# G474VET6_Penguins_v1_0.net
KiCad netlist of a schematic drawn in EasyEDA Pro
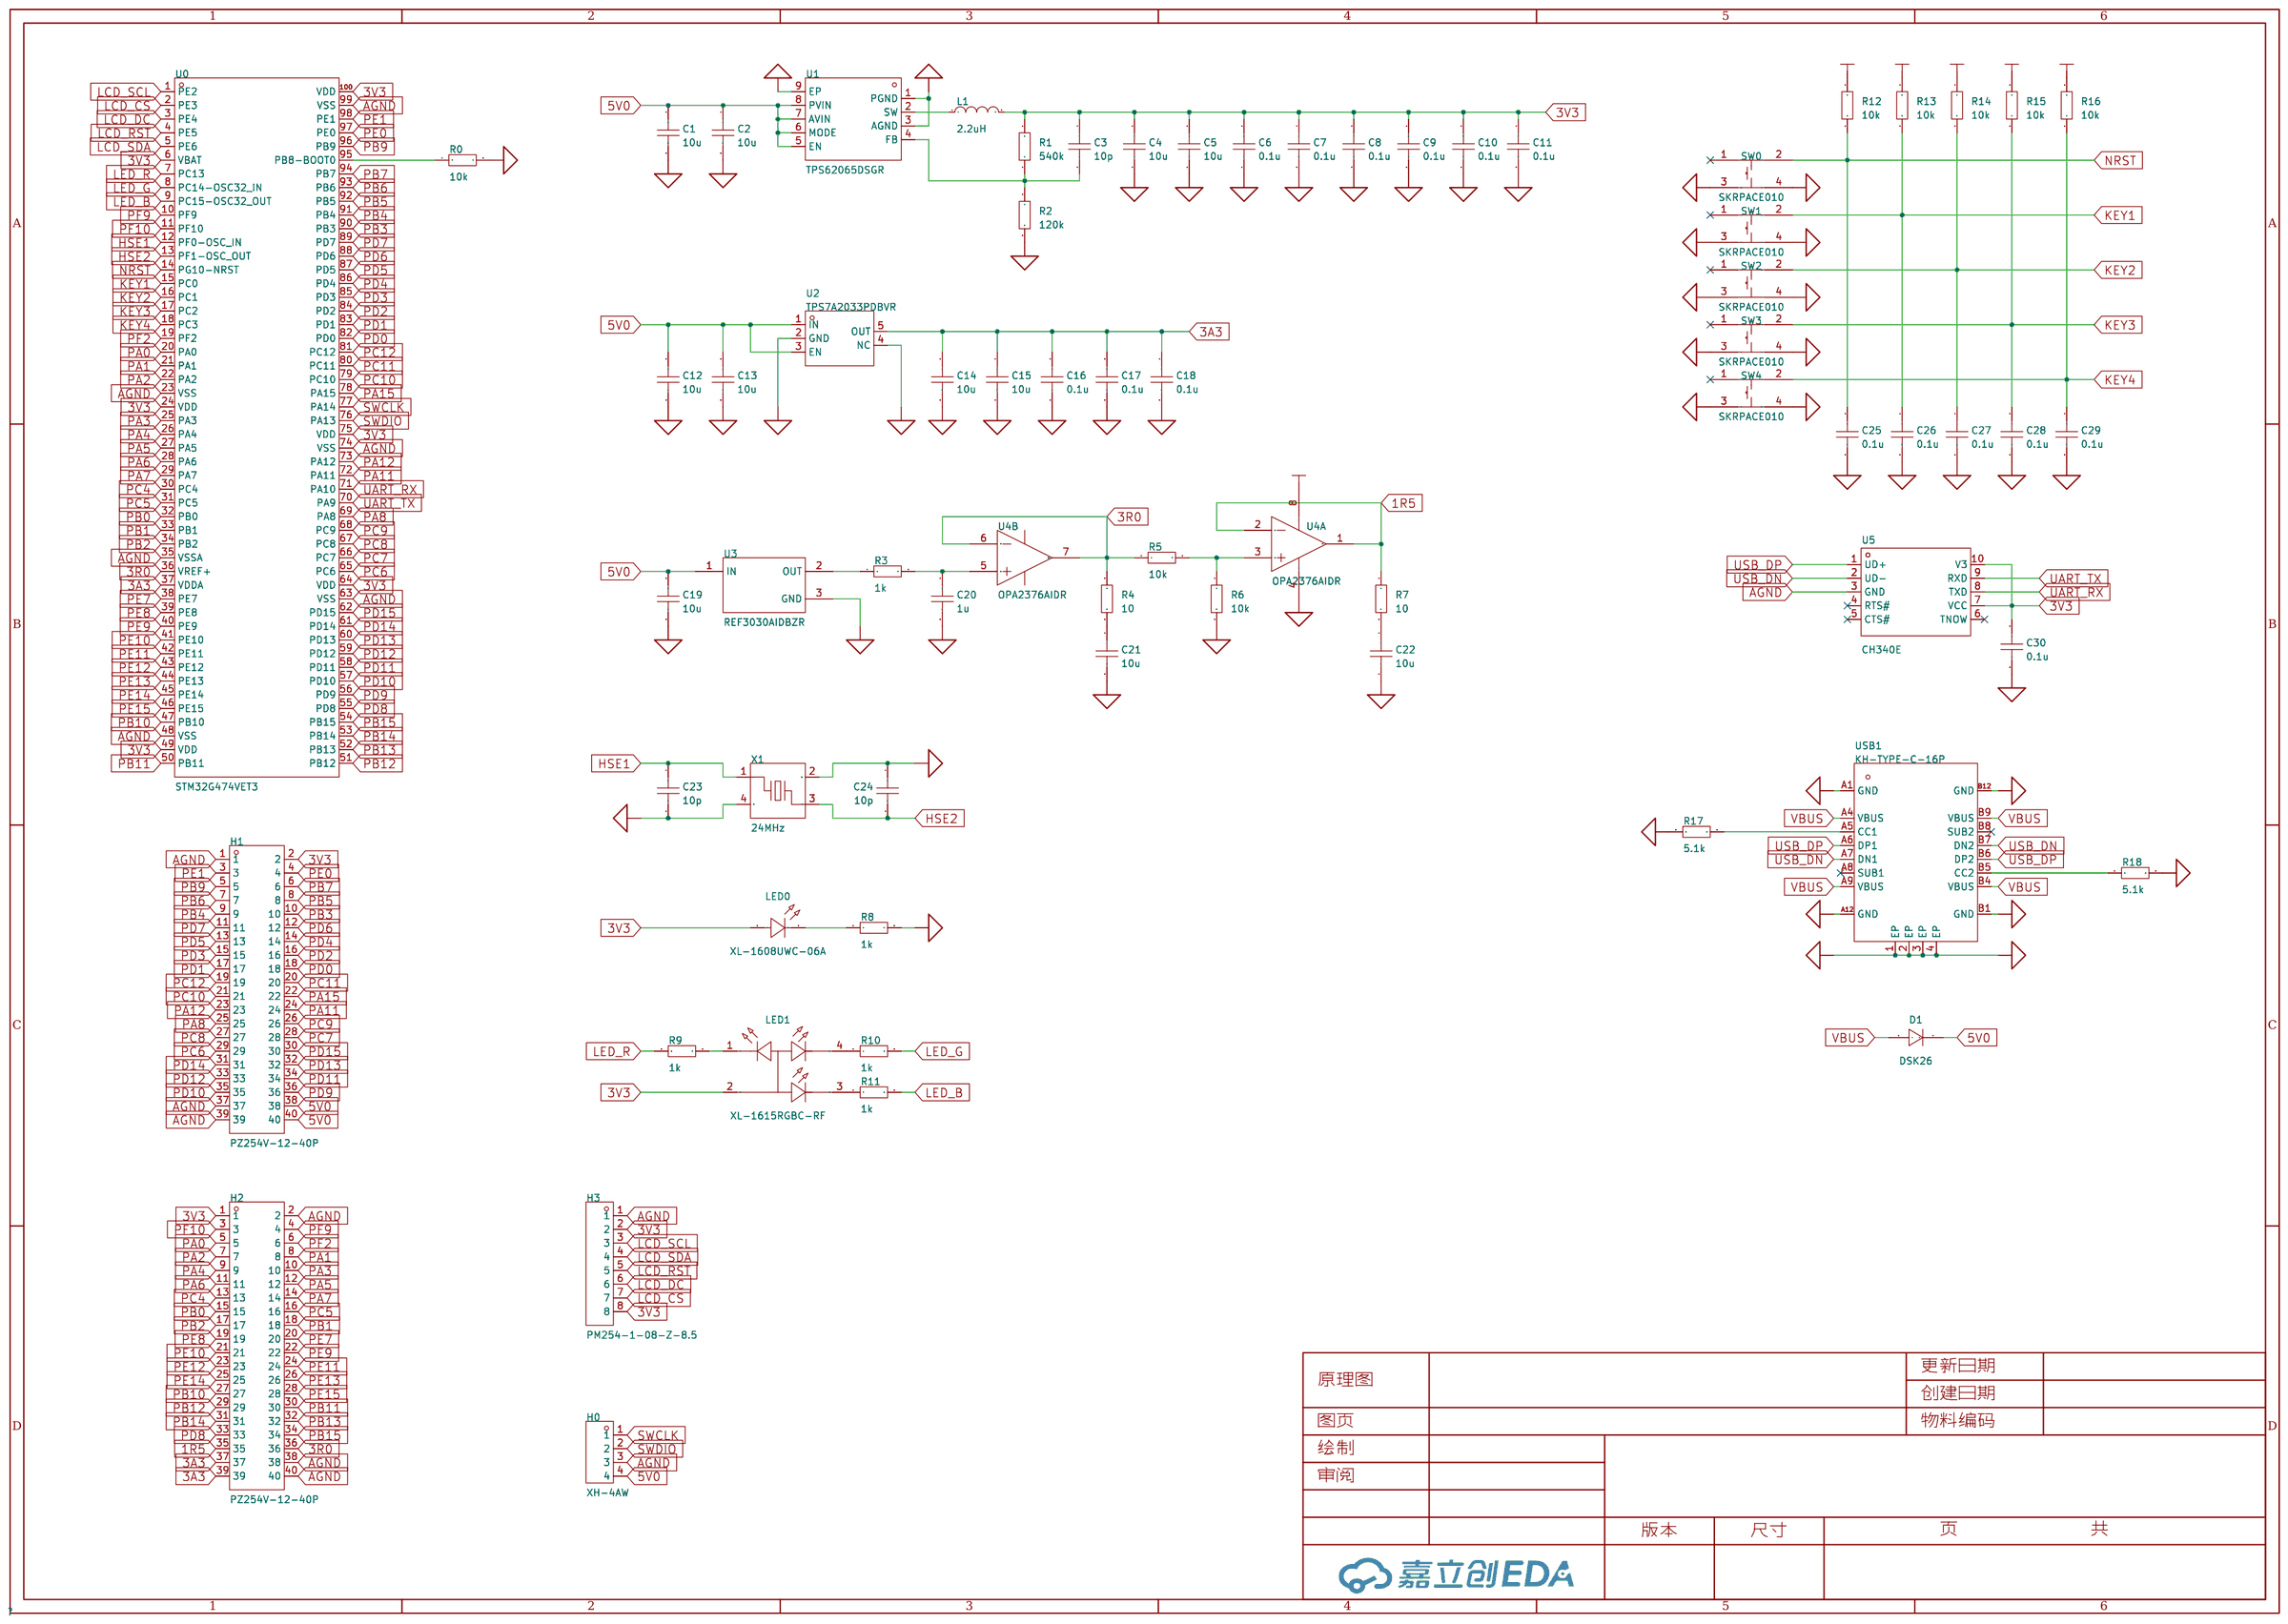
[diagram p0: schematic sheet]

(export (version "E")
  (design (tool "Eeschema 10.0.6"))
  (components
    (comp (ref "C1")
      (value "10u")
      (footprint "easyedapro:C0603")
      (libsource (lib "easyedapro") (part "CapAcitance"))
    )
    (comp (ref "C2")
      (value "10u")
      (footprint "easyedapro:C0603")
      (libsource (lib "easyedapro") (part "CapAcitance"))
    )
    (comp (ref "C3")
      (value "10p")
      (footprint "easyedapro:C0603")
      (libsource (lib "easyedapro") (part "CapAcitance"))
    )
    (comp (ref "C4")
      (value "10u")
      (footprint "easyedapro:C0603")
      (libsource (lib "easyedapro") (part "CapAcitance"))
    )
    (comp (ref "C5")
      (value "10u")
      (footprint "easyedapro:C0603")
      (libsource (lib "easyedapro") (part "CapAcitance"))
    )
    (comp (ref "C6")
      (value "0.1u")
      (footprint "easyedapro:C0603")
      (libsource (lib "easyedapro") (part "CapAcitance"))
    )
    (comp (ref "C7")
      (value "0.1u")
      (footprint "easyedapro:C0603")
      (libsource (lib "easyedapro") (part "CapAcitance"))
    )
    (comp (ref "C8")
      (value "0.1u")
      (footprint "easyedapro:C0603")
      (libsource (lib "easyedapro") (part "CapAcitance"))
    )
    (comp (ref "C9")
      (value "0.1u")
      (footprint "easyedapro:C0603")
      (libsource (lib "easyedapro") (part "CapAcitance"))
    )
    (comp (ref "C10")
      (value "0.1u")
      (footprint "easyedapro:C0603")
      (libsource (lib "easyedapro") (part "CapAcitance"))
    )
    (comp (ref "C11")
      (value "0.1u")
      (footprint "easyedapro:C0603")
      (libsource (lib "easyedapro") (part "CapAcitance"))
    )
    (comp (ref "C12")
      (value "10u")
      (footprint "easyedapro:C0603")
      (libsource (lib "easyedapro") (part "CapAcitance"))
    )
    (comp (ref "C13")
      (value "10u")
      (footprint "easyedapro:C0603")
      (libsource (lib "easyedapro") (part "CapAcitance"))
    )
    (comp (ref "C14")
      (value "10u")
      (footprint "easyedapro:C0603")
      (libsource (lib "easyedapro") (part "CapAcitance"))
    )
    (comp (ref "C15")
      (value "10u")
      (footprint "easyedapro:C0603")
      (libsource (lib "easyedapro") (part "CapAcitance"))
    )
    (comp (ref "C16")
      (value "0.1u")
      (footprint "easyedapro:C0603")
      (libsource (lib "easyedapro") (part "CapAcitance"))
    )
    (comp (ref "C17")
      (value "0.1u")
      (footprint "easyedapro:C0603")
      (libsource (lib "easyedapro") (part "CapAcitance"))
    )
    (comp (ref "C18")
      (value "0.1u")
      (footprint "easyedapro:C0603")
      (libsource (lib "easyedapro") (part "CapAcitance"))
    )
    (comp (ref "C19")
      (value "10u")
      (footprint "easyedapro:C0603")
      (libsource (lib "easyedapro") (part "CapAcitance"))
    )
    (comp (ref "C20")
      (value "1u")
      (footprint "easyedapro:C0603")
      (libsource (lib "easyedapro") (part "CapAcitance"))
    )
    (comp (ref "C21")
      (value "10u")
      (footprint "easyedapro:C0603")
      (libsource (lib "easyedapro") (part "CapAcitance"))
    )
    (comp (ref "C22")
      (value "10u")
      (footprint "easyedapro:C0603")
      (libsource (lib "easyedapro") (part "CapAcitance"))
    )
    (comp (ref "C23")
      (value "10p")
      (footprint "easyedapro:C0603")
      (libsource (lib "easyedapro") (part "CapAcitance"))
    )
    (comp (ref "C24")
      (value "10p")
      (footprint "easyedapro:C0603")
      (libsource (lib "easyedapro") (part "CapAcitance"))
    )
    (comp (ref "C25")
      (value "0.1u")
      (footprint "easyedapro:C0603")
      (libsource (lib "easyedapro") (part "CapAcitance"))
    )
    (comp (ref "C26")
      (value "0.1u")
      (footprint "easyedapro:C0603")
      (libsource (lib "easyedapro") (part "CapAcitance"))
    )
    (comp (ref "C27")
      (value "0.1u")
      (footprint "easyedapro:C0603")
      (libsource (lib "easyedapro") (part "CapAcitance"))
    )
    (comp (ref "C28")
      (value "0.1u")
      (footprint "easyedapro:C0603")
      (libsource (lib "easyedapro") (part "CapAcitance"))
    )
    (comp (ref "C29")
      (value "0.1u")
      (footprint "easyedapro:C0603")
      (libsource (lib "easyedapro") (part "CapAcitance"))
    )
    (comp (ref "C30")
      (value "0.1u")
      (footprint "easyedapro:C0603")
      (libsource (lib "easyedapro") (part "CapAcitance"))
    )
    (comp (ref "D1")
      (value "DSK26")
      (footprint "easyedapro:SOD-123_L2.8-W1.8-LS3.7-RD")
      (description "二极管配置:独立式;正向压降(Vf):700mV@2A;直流反向耐压(Vr):60V;整流电流:2A;")
      (fields (field (name "Manufacturer") "MDD(辰达半导体)"))
      (libsource (lib "easyedapro") (part "DSK26"))
    )
    (comp (ref "H0")
      (value "XH-4AW")
      (footprint "easyedapro:CONN-TH_XH-4AW")
      (fields (field (name "Manufacturer") "HCTL(华灿天禄)"))
      (libsource (lib "easyedapro") (part "XH-4AW_C2908613"))
    )
    (comp (ref "H1")
      (value "PZ254V-12-40P")
      (footprint "easyedapro:HDR-TH_40P-P2.54-V-M-R2-C20-S2.54_2-146257-0")
      (fields (field (name "Manufacturer") "XFCN(兴飞)"))
      (libsource (lib "easyedapro") (part "PZ254V-12-40P"))
    )
    (comp (ref "H2")
      (value "PZ254V-12-40P")
      (footprint "easyedapro:HDR-TH_40P-P2.54-V-M-R2-C20-S2.54_2-146257-0")
      (fields (field (name "Manufacturer") "XFCN(兴飞)"))
      (libsource (lib "easyedapro") (part "PZ254V-12-40P"))
    )
    (comp (ref "H3")
      (value "PM254-1-08-Z-8.5")
      (footprint "easyedapro:HDR-TH_8P-P2.54-V-F")
      (fields (field (name "Manufacturer") "HCTL(华灿天禄)"))
      (libsource (lib "easyedapro") (part "PM254-1-08-Z-8.5"))
    )
    (comp (ref "L1")
      (value "2.2uH")
      (footprint "easyedapro:IND-SMD_L2.5-W2.0")
      (description "电感值:2.2uH;精度:±20%;饱和电流(Isat):3A;类型:-;")
      (fields (field (name "Manufacturer Part") "SMMS252010-2R2M") (field (name "Manufacturer") "SXN(顺翔诺)"))
      (libsource (lib "easyedapro") (part "SMMS252010-2R2M"))
    )
    (comp (ref "LED0")
      (value "XL-1608UWC-06A")
      (footprint "easyedapro:LED0603-RD_1")
      (fields (field (name "Manufacturer") "XINGLIGHT(成兴光)"))
      (libsource (lib "easyedapro") (part "XL-1608UWC-06A"))
    )
    (comp (ref "LED1")
      (value "XL-1615RGBC-RF")
      (footprint "easyedapro:LED-ARRAY-SMD_4P-L1.6-W1.5-BR_XL-1615RGBC-RF")
      (fields (field (name "Manufacturer") "XINGLIGHT(成兴光)"))
      (libsource (lib "easyedapro") (part "XL-1615RGBC-RF"))
    )
    (comp (ref "R0") (value "10k") (footprint "easyedapro:R0603") (libsource (lib "easyedapro") (part "电阻")))
    (comp (ref "R1") (value "540k") (footprint "easyedapro:R0603") (libsource (lib "easyedapro") (part "电阻")))
    (comp (ref "R2") (value "120k") (footprint "easyedapro:R0603") (libsource (lib "easyedapro") (part "电阻")))
    (comp (ref "R3") (value "1k") (footprint "easyedapro:R0603") (libsource (lib "easyedapro") (part "电阻")))
    (comp (ref "R4") (value "10") (footprint "easyedapro:R0603") (libsource (lib "easyedapro") (part "电阻")))
    (comp (ref "R5") (value "10k") (footprint "easyedapro:R0603") (libsource (lib "easyedapro") (part "电阻")))
    (comp (ref "R6") (value "10k") (footprint "easyedapro:R0603") (libsource (lib "easyedapro") (part "电阻")))
    (comp (ref "R7") (value "10") (footprint "easyedapro:R0603") (libsource (lib "easyedapro") (part "电阻")))
    (comp (ref "R8") (value "1k") (footprint "easyedapro:R0603") (libsource (lib "easyedapro") (part "电阻")))
    (comp (ref "R9") (value "1k") (footprint "easyedapro:R0603") (libsource (lib "easyedapro") (part "电阻")))
    (comp (ref "R10") (value "1k") (footprint "easyedapro:R0603") (libsource (lib "easyedapro") (part "电阻")))
    (comp (ref "R11") (value "1k") (footprint "easyedapro:R0603") (libsource (lib "easyedapro") (part "电阻")))
    (comp (ref "R12") (value "10k") (footprint "easyedapro:R0603") (libsource (lib "easyedapro") (part "电阻")))
    (comp (ref "R13") (value "10k") (footprint "easyedapro:R0603") (libsource (lib "easyedapro") (part "电阻")))
    (comp (ref "R14") (value "10k") (footprint "easyedapro:R0603") (libsource (lib "easyedapro") (part "电阻")))
    (comp (ref "R15") (value "10k") (footprint "easyedapro:R0603") (libsource (lib "easyedapro") (part "电阻")))
    (comp (ref "R16") (value "10k") (footprint "easyedapro:R0603") (libsource (lib "easyedapro") (part "电阻")))
    (comp (ref "R17")
      (value "5.1k")
      (footprint "easyedapro:R0603")
      (libsource (lib "easyedapro") (part "电阻"))
    )
    (comp (ref "R18")
      (value "5.1k")
      (footprint "easyedapro:R0603")
      (libsource (lib "easyedapro") (part "电阻"))
    )
    (comp (ref "SW0")
      (value "SKRPACE010")
      (footprint "easyedapro:KEY-SMD_4P-L4.2-W3.2-P2.20-LS4.6")
      (description "电路结构:单刀单掷;按钮形状:椭圆形按钮;安装方式:立贴;开关长度:4.2mm;开关宽度:3.2mm;开关高度:2.5mm;触点电流:50mA;额定电压(DC):16V;带灯:-;机械寿命:-;")
      (fields (field (name "Manufacturer") "ALPSALPINE(阿尔卑斯阿尔派)"))
      (libsource (lib "easyedapro") (part "SKRPACE010"))
    )
    (comp (ref "SW1")
      (value "SKRPACE010")
      (footprint "easyedapro:KEY-SMD_4P-L4.2-W3.2-P2.20-LS4.6")
      (description "电路结构:单刀单掷;按钮形状:椭圆形按钮;安装方式:立贴;开关长度:4.2mm;开关宽度:3.2mm;开关高度:2.5mm;触点电流:50mA;额定电压(DC):16V;带灯:-;机械寿命:-;")
      (fields (field (name "Manufacturer") "ALPSALPINE(阿尔卑斯阿尔派)"))
      (libsource (lib "easyedapro") (part "SKRPACE010"))
    )
    (comp (ref "SW2")
      (value "SKRPACE010")
      (footprint "easyedapro:KEY-SMD_4P-L4.2-W3.2-P2.20-LS4.6")
      (description "电路结构:单刀单掷;按钮形状:椭圆形按钮;安装方式:立贴;开关长度:4.2mm;开关宽度:3.2mm;开关高度:2.5mm;触点电流:50mA;额定电压(DC):16V;带灯:-;机械寿命:-;")
      (fields (field (name "Manufacturer") "ALPSALPINE(阿尔卑斯阿尔派)"))
      (libsource (lib "easyedapro") (part "SKRPACE010"))
    )
    (comp (ref "SW3")
      (value "SKRPACE010")
      (footprint "easyedapro:KEY-SMD_4P-L4.2-W3.2-P2.20-LS4.6")
      (description "电路结构:单刀单掷;按钮形状:椭圆形按钮;安装方式:立贴;开关长度:4.2mm;开关宽度:3.2mm;开关高度:2.5mm;触点电流:50mA;额定电压(DC):16V;带灯:-;机械寿命:-;")
      (fields (field (name "Manufacturer") "ALPSALPINE(阿尔卑斯阿尔派)"))
      (libsource (lib "easyedapro") (part "SKRPACE010"))
    )
    (comp (ref "SW4")
      (value "SKRPACE010")
      (footprint "easyedapro:KEY-SMD_4P-L4.2-W3.2-P2.20-LS4.6")
      (description "电路结构:单刀单掷;按钮形状:椭圆形按钮;安装方式:立贴;开关长度:4.2mm;开关宽度:3.2mm;开关高度:2.5mm;触点电流:50mA;额定电压(DC):16V;带灯:-;机械寿命:-;")
      (fields (field (name "Manufacturer") "ALPSALPINE(阿尔卑斯阿尔派)"))
      (libsource (lib "easyedapro") (part "SKRPACE010"))
    )
    (comp (ref "U0")
      (value "STM32G474VET3")
      (footprint "easyedapro:LQFP-100_L14.0-W14.0-P0.50-LS16.0-BL")
      (description "CPU内核:ARM-M系列;CPU最大主频:170MHz;应用领域:-;")
      (fields (field (name "Manufacturer") "ST(意法半导体)"))
      (libsource (lib "easyedapro") (part "STM32G474VET3"))
    )
    (comp (ref "U1")
      (value "TPS62065DSGR")
      (footprint "easyedapro:WSON-8_L2.0-W2.0-P0.65-BL-EP")
      (description "功能类型:降压型;输出类型:可调;工作电压:2.9V~6V;输出电压:-;输出电流:2A;")
      (fields (field (name "Manufacturer") "TI(德州仪器)"))
      (libsource (lib "easyedapro") (part "TPS62065DSGR"))
    )
    (comp (ref "U2")
      (value "TPS7A2033PDBVR")
      (footprint "easyedapro:SOT-23-5_L2.9-W1.6-P0.95-LS2.8-BR")
      (description "输出类型:固定;最大输入电压:6V;输出电压:3.3V;输出电流:300mA;输出极性:正极;")
      (fields (field (name "Manufacturer") "TI(德州仪器)"))
      (libsource (lib "easyedapro") (part "TPS7A2033PDBVR"))
    )
    (comp (ref "U3")
      (value "REF3030AIDBZR")
      (footprint "easyedapro:SOT-23-3_L2.9-W1.6-P1.90-LS2.8-BR")
      (description "输出类型:固定;输入电压:3.05V~5.5V;输出电压:3V;输出电流:25mA;精度:±0.2%;")
      (fields (field (name "Manufacturer") "TI(德州仪器)"))
      (libsource (lib "easyedapro") (part "REF3030AIDBZR"))
    )
    (comp (ref "U4")
      (value "OPA2376AIDR")
      (footprint "easyedapro:SOIC-8_L4.9-W3.9-P1.27-LS6.0-BL")
      (description "放大器数:双路;增益带宽积(GBP):5.5MHz;输入偏置电流(Ib):0.2pA;压摆率(SR):2V/us;轨到轨:-;")
      (fields (field (name "Manufacturer") "TI(德州仪器)"))
      (libsource (lib "easyedapro") (part "OPA2376AID"))
    )
    (comp (ref "U5")
      (value "CH340E")
      (footprint "easyedapro:MSOP-10_L3.0-W3.0-P0.50-LS5.0-BL")
      (description "应用功能:收发器;接口协议:USB 2.0;数据速率:2Mbps;")
      (fields (field (name "Manufacturer") "WCH(南京沁恒)"))
      (libsource (lib "easyedapro") (part "CH340E"))
    )
    (comp (ref "USB1")
      (value "KH-TYPE-C-16P")
      (footprint "easyedapro:USB-C-SMD_KH-TYPE-C-16P")
      (description "连接器类型:Type-C;标准:-;公母:母;端口数量:1;触点数量:16P;安装方式:卧贴;额定电流 - 电源:3A;工作温度范围:-40°C~+85°C;")
      (fields (field (name "Manufacturer") "kinghelm(金航标)"))
      (libsource (lib "easyedapro") (part "KH-TYPE-C-16P"))
    )
    (comp (ref "X1")
      (value "24MHz")
      (footprint "easyedapro:CRYSTAL-SMD_4P-L2.0-W1.6-BL")
      (description "晶振类型:贴片晶振;频率:24MHz;常温频差:±10ppm;负载电容:10pF;频率稳定度:±20ppm;")
      (fields
        (field (name "Manufacturer Part") "XL7EL89CMI-111YLC-24M")
        (field (name "Manufacturer") "YXC(扬兴晶振)")
      )
      (libsource (lib "easyedapro") (part "XL7EL89CMI-111YLC-24M"))
    )
  )
  (nets
    (net (code "1") (name "1R5") (class "Default")
      (node (ref "H2") (pin "35") (pinfunction "35_35") (pintype "unspecified"))
      (node (ref "R7") (pin "1") (pinfunction "1_1") (pintype "input"))
      (node (ref "U4") (pin "1") (pinfunction "OUT_A_1") (pintype "output"))
      (node (ref "U4") (pin "2") (pinfunction "IN_A-_2") (pintype "unspecified"))
    )
    (net (code "2") (name "3A3") (class "Default")
      (node (ref "C14") (pin "1") (pinfunction "1_1") (pintype "input"))
      (node (ref "C15") (pin "1") (pinfunction "1_1") (pintype "input"))
      (node (ref "C16") (pin "1") (pinfunction "1_1") (pintype "input"))
      (node (ref "C17") (pin "1") (pinfunction "1_1") (pintype "input"))
      (node (ref "C18") (pin "1") (pinfunction "1_1") (pintype "input"))
      (node (ref "H2") (pin "37") (pinfunction "37_37") (pintype "unspecified"))
      (node (ref "H2") (pin "39") (pinfunction "39_39") (pintype "unspecified"))
      (node (ref "U0") (pin "37") (pinfunction "VDDA_37") (pintype "unspecified"))
      (node (ref "U2") (pin "5") (pinfunction "OUT_5") (pintype "unspecified"))
      (node (ref "U4") (pin "8") (pinfunction "V+_8") (pintype "unspecified"))
    )
    (net (code "3") (name "3R0") (class "Default")
      (node (ref "H2") (pin "36") (pinfunction "36_36") (pintype "unspecified"))
      (node (ref "R4") (pin "1") (pinfunction "1_1") (pintype "input"))
      (node (ref "R5") (pin "1") (pinfunction "1_1") (pintype "input"))
      (node (ref "U0") (pin "36") (pinfunction "VREF+_36") (pintype "unspecified"))
      (node (ref "U4") (pin "6") (pinfunction "IN_B-_6") (pintype "unspecified"))
      (node (ref "U4") (pin "7") (pinfunction "OUT_B_7") (pintype "output"))
    )
    (net (code "4") (name "3V3") (class "Default")
      (node (ref "C10") (pin "1") (pinfunction "1_1") (pintype "input"))
      (node (ref "C11") (pin "1") (pinfunction "1_1") (pintype "input"))
      (node (ref "C3") (pin "1") (pinfunction "1_1") (pintype "input"))
      (node (ref "C30") (pin "1") (pinfunction "1_1") (pintype "input"))
      (node (ref "C4") (pin "1") (pinfunction "1_1") (pintype "input"))
      (node (ref "C5") (pin "1") (pinfunction "1_1") (pintype "input"))
      (node (ref "C6") (pin "1") (pinfunction "1_1") (pintype "input"))
      (node (ref "C7") (pin "1") (pinfunction "1_1") (pintype "input"))
      (node (ref "C8") (pin "1") (pinfunction "1_1") (pintype "input"))
      (node (ref "C9") (pin "1") (pinfunction "1_1") (pintype "input"))
      (node (ref "H1") (pin "2") (pinfunction "2_2") (pintype "unspecified"))
      (node (ref "H2") (pin "1") (pinfunction "1_1") (pintype "unspecified"))
      (node (ref "H3") (pin "2") (pinfunction "2_2") (pintype "unspecified"))
      (node (ref "H3") (pin "8") (pinfunction "8_8") (pintype "unspecified"))
      (node (ref "L1") (pin "2") (pinfunction "2_2") (pintype "unspecified"))
      (node (ref "LED0") (pin "2") (pinfunction "A_2") (pintype "unspecified"))
      (node (ref "LED1") (pin "2") (pinfunction "COM+_2") (pintype "unspecified"))
      (node (ref "R1") (pin "1") (pinfunction "1_1") (pintype "input"))
      (node (ref "R12") (pin "1") (pinfunction "1_1") (pintype "input"))
      (node (ref "R13") (pin "1") (pinfunction "1_1") (pintype "input"))
      (node (ref "R14") (pin "1") (pinfunction "1_1") (pintype "input"))
      (node (ref "R15") (pin "1") (pinfunction "1_1") (pintype "input"))
      (node (ref "R16") (pin "1") (pinfunction "1_1") (pintype "input"))
      (node (ref "U0") (pin "100") (pinfunction "VDD_100") (pintype "unspecified"))
      (node (ref "U0") (pin "24") (pinfunction "VDD_24") (pintype "unspecified"))
      (node (ref "U0") (pin "49") (pinfunction "VDD_49") (pintype "unspecified"))
      (node (ref "U0") (pin "6") (pinfunction "VBAT_6") (pintype "unspecified"))
      (node (ref "U0") (pin "64") (pinfunction "VDD_64") (pintype "unspecified"))
      (node (ref "U0") (pin "75") (pinfunction "VDD_75") (pintype "unspecified"))
      (node (ref "U5") (pin "10") (pinfunction "V3_10") (pintype "unspecified"))
      (node (ref "U5") (pin "7") (pinfunction "VCC_7") (pintype "unspecified"))
    )
    (net (code "5") (name "5V0") (class "Default")
      (node (ref "C1") (pin "1") (pinfunction "1_1") (pintype "input"))
      (node (ref "C12") (pin "1") (pinfunction "1_1") (pintype "input"))
      (node (ref "C13") (pin "1") (pinfunction "1_1") (pintype "input"))
      (node (ref "C19") (pin "1") (pinfunction "1_1") (pintype "input"))
      (node (ref "C2") (pin "1") (pinfunction "1_1") (pintype "input"))
      (node (ref "D1") (pin "1") (pinfunction "K_1") (pintype "unspecified"))
      (node (ref "H0") (pin "4") (pinfunction "4_4") (pintype "unspecified"))
      (node (ref "H1") (pin "38") (pinfunction "38_38") (pintype "unspecified"))
      (node (ref "H1") (pin "40") (pinfunction "40_40") (pintype "unspecified"))
      (node (ref "U1") (pin "5") (pinfunction "EN_5") (pintype "unspecified"))
      (node (ref "U1") (pin "6") (pinfunction "MODE_6") (pintype "unspecified"))
      (node (ref "U1") (pin "7") (pinfunction "AVIN_7") (pintype "unspecified"))
      (node (ref "U1") (pin "8") (pinfunction "PVIN_8") (pintype "unspecified"))
      (node (ref "U2") (pin "1") (pinfunction "IN_1") (pintype "unspecified"))
      (node (ref "U2") (pin "3") (pinfunction "EN_3") (pintype "unspecified"))
      (node (ref "U3") (pin "1") (pinfunction "IN_1") (pintype "unspecified"))
    )
    (net (code "6") (name "AGND") (class "Default")
      (node (ref "C1") (pin "2") (pinfunction "2_2") (pintype "input"))
      (node (ref "C10") (pin "2") (pinfunction "2_2") (pintype "input"))
      (node (ref "C11") (pin "2") (pinfunction "2_2") (pintype "input"))
      (node (ref "C12") (pin "2") (pinfunction "2_2") (pintype "input"))
      (node (ref "C13") (pin "2") (pinfunction "2_2") (pintype "input"))
      (node (ref "C14") (pin "2") (pinfunction "2_2") (pintype "input"))
      (node (ref "C15") (pin "2") (pinfunction "2_2") (pintype "input"))
      (node (ref "C16") (pin "2") (pinfunction "2_2") (pintype "input"))
      (node (ref "C17") (pin "2") (pinfunction "2_2") (pintype "input"))
      (node (ref "C18") (pin "2") (pinfunction "2_2") (pintype "input"))
      (node (ref "C19") (pin "2") (pinfunction "2_2") (pintype "input"))
      (node (ref "C2") (pin "2") (pinfunction "2_2") (pintype "input"))
      (node (ref "C20") (pin "2") (pinfunction "2_2") (pintype "input"))
      (node (ref "C21") (pin "2") (pinfunction "2_2") (pintype "input"))
      (node (ref "C22") (pin "2") (pinfunction "2_2") (pintype "input"))
      (node (ref "C23") (pin "2") (pinfunction "2_2") (pintype "input"))
      (node (ref "C24") (pin "1") (pinfunction "1_1") (pintype "input"))
      (node (ref "C25") (pin "2") (pinfunction "2_2") (pintype "input"))
      (node (ref "C26") (pin "2") (pinfunction "2_2") (pintype "input"))
      (node (ref "C27") (pin "2") (pinfunction "2_2") (pintype "input"))
      (node (ref "C28") (pin "2") (pinfunction "2_2") (pintype "input"))
      (node (ref "C29") (pin "2") (pinfunction "2_2") (pintype "input"))
      (node (ref "C30") (pin "2") (pinfunction "2_2") (pintype "input"))
      (node (ref "C4") (pin "2") (pinfunction "2_2") (pintype "input"))
      (node (ref "C5") (pin "2") (pinfunction "2_2") (pintype "input"))
      (node (ref "C6") (pin "2") (pinfunction "2_2") (pintype "input"))
      (node (ref "C7") (pin "2") (pinfunction "2_2") (pintype "input"))
      (node (ref "C8") (pin "2") (pinfunction "2_2") (pintype "input"))
      (node (ref "C9") (pin "2") (pinfunction "2_2") (pintype "input"))
      (node (ref "H0") (pin "3") (pinfunction "3_3") (pintype "unspecified"))
      (node (ref "H1") (pin "1") (pinfunction "1_1") (pintype "unspecified"))
      (node (ref "H1") (pin "37") (pinfunction "37_37") (pintype "unspecified"))
      (node (ref "H1") (pin "39") (pinfunction "39_39") (pintype "unspecified"))
      (node (ref "H2") (pin "2") (pinfunction "2_2") (pintype "unspecified"))
      (node (ref "H2") (pin "38") (pinfunction "38_38") (pintype "unspecified"))
      (node (ref "H2") (pin "40") (pinfunction "40_40") (pintype "unspecified"))
      (node (ref "H3") (pin "1") (pinfunction "1_1") (pintype "unspecified"))
      (node (ref "R0") (pin "2") (pinfunction "2_2") (pintype "input"))
      (node (ref "R17") (pin "2") (pinfunction "2_2") (pintype "input"))
      (node (ref "R18") (pin "2") (pinfunction "2_2") (pintype "input"))
      (node (ref "R2") (pin "2") (pinfunction "2_2") (pintype "input"))
      (node (ref "R6") (pin "2") (pinfunction "2_2") (pintype "input"))
      (node (ref "R8") (pin "2") (pinfunction "2_2") (pintype "input"))
      (node (ref "SW0") (pin "3") (pinfunction "3_3") (pintype "unspecified"))
      (node (ref "SW0") (pin "4") (pinfunction "4_4") (pintype "unspecified"))
      (node (ref "SW1") (pin "3") (pinfunction "3_3") (pintype "unspecified"))
      (node (ref "SW1") (pin "4") (pinfunction "4_4") (pintype "unspecified"))
      (node (ref "SW2") (pin "3") (pinfunction "3_3") (pintype "unspecified"))
      (node (ref "SW2") (pin "4") (pinfunction "4_4") (pintype "unspecified"))
      (node (ref "SW3") (pin "3") (pinfunction "3_3") (pintype "unspecified"))
      (node (ref "SW3") (pin "4") (pinfunction "4_4") (pintype "unspecified"))
      (node (ref "SW4") (pin "3") (pinfunction "3_3") (pintype "unspecified"))
      (node (ref "SW4") (pin "4") (pinfunction "4_4") (pintype "unspecified"))
      (node (ref "U0") (pin "23") (pinfunction "VSS_23") (pintype "unspecified"))
      (node (ref "U0") (pin "35") (pinfunction "VSSA_35") (pintype "unspecified"))
      (node (ref "U0") (pin "48") (pinfunction "VSS_48") (pintype "unspecified"))
      (node (ref "U0") (pin "63") (pinfunction "VSS_63") (pintype "unspecified"))
      (node (ref "U0") (pin "74") (pinfunction "VSS_74") (pintype "unspecified"))
      (node (ref "U0") (pin "99") (pinfunction "VSS_99") (pintype "unspecified"))
      (node (ref "U1") (pin "1") (pinfunction "PGND_1") (pintype "unspecified"))
      (node (ref "U1") (pin "3") (pinfunction "AGND_3") (pintype "unspecified"))
      (node (ref "U1") (pin "9") (pinfunction "EP_9") (pintype "unspecified"))
      (node (ref "U2") (pin "2") (pinfunction "GND_2") (pintype "unspecified"))
      (node (ref "U2") (pin "4") (pinfunction "NC_4") (pintype "unspecified"))
      (node (ref "U3") (pin "3") (pinfunction "GND_3") (pintype "unspecified"))
      (node (ref "U4") (pin "4") (pinfunction "V-_4") (pintype "unspecified"))
      (node (ref "U5") (pin "3") (pinfunction "GND_3") (pintype "unspecified"))
      (node (ref "USB1") (pin "1") (pinfunction "EP_1") (pintype "unspecified"))
      (node (ref "USB1") (pin "2") (pinfunction "EP_2") (pintype "unspecified"))
      (node (ref "USB1") (pin "3") (pinfunction "EP_3") (pintype "unspecified"))
      (node (ref "USB1") (pin "4") (pinfunction "EP_4") (pintype "unspecified"))
      (node (ref "USB1") (pin "A1") (pinfunction "GND_A1") (pintype "unspecified"))
      (node (ref "USB1") (pin "A12") (pinfunction "GND_A12") (pintype "unspecified"))
      (node (ref "USB1") (pin "B1") (pinfunction "GND_B1") (pintype "unspecified"))
      (node (ref "USB1") (pin "B12") (pinfunction "GND_B12") (pintype "unspecified"))
      (node (ref "X1") (pin "2") (pinfunction "GND_2") (pintype "input"))
      (node (ref "X1") (pin "4") (pinfunction "GND_4") (pintype "input"))
    )
    (net (code "7") (name "HSE1") (class "Default")
      (node (ref "C23") (pin "1") (pinfunction "1_1") (pintype "input"))
      (node (ref "U0") (pin "12") (pinfunction "PF0-OSC_IN_12") (pintype "unspecified"))
      (node (ref "X1") (pin "1") (pinfunction "1_1") (pintype "input"))
    )
    (net (code "8") (name "HSE2") (class "Default")
      (node (ref "C24") (pin "2") (pinfunction "2_2") (pintype "input"))
      (node (ref "U0") (pin "13") (pinfunction "PF1-OSC_OUT_13") (pintype "unspecified"))
      (node (ref "X1") (pin "3") (pinfunction "3_3") (pintype "input"))
    )
    (net (code "9") (name "KEY1") (class "Default")
      (node (ref "C26") (pin "1") (pinfunction "1_1") (pintype "input"))
      (node (ref "R13") (pin "2") (pinfunction "2_2") (pintype "input"))
      (node (ref "SW1") (pin "2") (pinfunction "2_2") (pintype "unspecified"))
      (node (ref "U0") (pin "15") (pinfunction "PC0_15") (pintype "unspecified"))
    )
    (net (code "10") (name "KEY2") (class "Default")
      (node (ref "C27") (pin "1") (pinfunction "1_1") (pintype "input"))
      (node (ref "R14") (pin "2") (pinfunction "2_2") (pintype "input"))
      (node (ref "SW2") (pin "2") (pinfunction "2_2") (pintype "unspecified"))
      (node (ref "U0") (pin "16") (pinfunction "PC1_16") (pintype "unspecified"))
    )
    (net (code "11") (name "KEY3") (class "Default")
      (node (ref "C28") (pin "1") (pinfunction "1_1") (pintype "input"))
      (node (ref "R15") (pin "2") (pinfunction "2_2") (pintype "input"))
      (node (ref "SW3") (pin "2") (pinfunction "2_2") (pintype "unspecified"))
      (node (ref "U0") (pin "17") (pinfunction "PC2_17") (pintype "unspecified"))
    )
    (net (code "12") (name "KEY4") (class "Default")
      (node (ref "C29") (pin "1") (pinfunction "1_1") (pintype "input"))
      (node (ref "R16") (pin "2") (pinfunction "2_2") (pintype "input"))
      (node (ref "SW4") (pin "2") (pinfunction "2_2") (pintype "unspecified"))
      (node (ref "U0") (pin "18") (pinfunction "PC3_18") (pintype "unspecified"))
    )
    (net (code "13") (name "LCD_CS") (class "Default")
      (node (ref "H3") (pin "7") (pinfunction "7_7") (pintype "unspecified"))
      (node (ref "U0") (pin "2") (pinfunction "PE3_2") (pintype "unspecified"))
    )
    (net (code "14") (name "LCD_DC") (class "Default")
      (node (ref "H3") (pin "6") (pinfunction "6_6") (pintype "unspecified"))
      (node (ref "U0") (pin "3") (pinfunction "PE4_3") (pintype "unspecified"))
    )
    (net (code "15") (name "LCD_RST") (class "Default")
      (node (ref "H3") (pin "5") (pinfunction "5_5") (pintype "unspecified"))
      (node (ref "U0") (pin "4") (pinfunction "PE5_4") (pintype "unspecified"))
    )
    (net (code "16") (name "LCD_SCL") (class "Default")
      (node (ref "H3") (pin "3") (pinfunction "3_3") (pintype "unspecified"))
      (node (ref "U0") (pin "1") (pinfunction "PE2_1") (pintype "unspecified"))
    )
    (net (code "17") (name "LCD_SDA") (class "Default")
      (node (ref "H3") (pin "4") (pinfunction "4_4") (pintype "unspecified"))
      (node (ref "U0") (pin "5") (pinfunction "PE6_5") (pintype "unspecified"))
    )
    (net (code "18") (name "LED_B") (class "Default")
      (node (ref "R11") (pin "2") (pinfunction "2_2") (pintype "input"))
      (node (ref "U0") (pin "9") (pinfunction "PC15-OSC32_OUT_9") (pintype "unspecified"))
    )
    (net (code "19") (name "LED_G") (class "Default")
      (node (ref "R10") (pin "2") (pinfunction "2_2") (pintype "input"))
      (node (ref "U0") (pin "8") (pinfunction "PC14-OSC32_IN_8") (pintype "unspecified"))
    )
    (net (code "20") (name "LED_R") (class "Default")
      (node (ref "R9") (pin "2") (pinfunction "2_2") (pintype "input"))
      (node (ref "U0") (pin "7") (pinfunction "PC13_7") (pintype "unspecified"))
    )
    (net (code "21") (name "NRST") (class "Default")
      (node (ref "C25") (pin "1") (pinfunction "1_1") (pintype "input"))
      (node (ref "R12") (pin "2") (pinfunction "2_2") (pintype "input"))
      (node (ref "SW0") (pin "2") (pinfunction "2_2") (pintype "unspecified"))
      (node (ref "U0") (pin "14") (pinfunction "PG10-NRST_14") (pintype "unspecified"))
    )
    (net (code "22") (name "Net-(C21-Pad1)") (class "Default")
      (node (ref "C21") (pin "1") (pinfunction "1_1") (pintype "input"))
      (node (ref "R4") (pin "2") (pinfunction "2_2") (pintype "input"))
    )
    (net (code "23") (name "Net-(C22-Pad1)") (class "Default")
      (node (ref "C22") (pin "1") (pinfunction "1_1") (pintype "input"))
      (node (ref "R7") (pin "2") (pinfunction "2_2") (pintype "input"))
    )
    (net (code "24") (name "Net-(LED0-K)") (class "Default")
      (node (ref "LED0") (pin "1") (pinfunction "K_1") (pintype "unspecified"))
      (node (ref "R8") (pin "1") (pinfunction "1_1") (pintype "input"))
    )
    (net (code "25") (name "Net-(LED1-B-)") (class "Default")
      (node (ref "LED1") (pin "3") (pinfunction "B-_3") (pintype "unspecified"))
      (node (ref "R11") (pin "1") (pinfunction "1_1") (pintype "input"))
    )
    (net (code "26") (name "Net-(LED1-G-)") (class "Default")
      (node (ref "LED1") (pin "4") (pinfunction "G-_4") (pintype "unspecified"))
      (node (ref "R10") (pin "1") (pinfunction "1_1") (pintype "input"))
    )
    (net (code "27") (name "Net-(LED1-R-)") (class "Default")
      (node (ref "LED1") (pin "1") (pinfunction "R-_1") (pintype "unspecified"))
      (node (ref "R9") (pin "1") (pinfunction "1_1") (pintype "input"))
    )
    (net (code "28") (name "Net-(U0-PB8-BOOT0)") (class "Default")
      (node (ref "R0") (pin "1") (pinfunction "1_1") (pintype "input"))
      (node (ref "U0") (pin "95") (pinfunction "PB8-BOOT0_95") (pintype "unspecified"))
    )
    (net (code "29") (name "Net-(U1-FB)") (class "Default")
      (node (ref "C3") (pin "2") (pinfunction "2_2") (pintype "input"))
      (node (ref "R1") (pin "2") (pinfunction "2_2") (pintype "input"))
      (node (ref "R2") (pin "1") (pinfunction "1_1") (pintype "input"))
      (node (ref "U1") (pin "4") (pinfunction "FB_4") (pintype "unspecified"))
    )
    (net (code "30") (name "Net-(U1-SW)") (class "Default")
      (node (ref "L1") (pin "1") (pinfunction "1_1") (pintype "unspecified"))
      (node (ref "U1") (pin "2") (pinfunction "SW_2") (pintype "unspecified"))
    )
    (net (code "31") (name "Net-(U3-OUT)") (class "Default")
      (node (ref "R3") (pin "1") (pinfunction "1_1") (pintype "input"))
      (node (ref "U3") (pin "2") (pinfunction "OUT_2") (pintype "unspecified"))
    )
    (net (code "32") (name "Net-(U4A-IN_A+)") (class "Default")
      (node (ref "R5") (pin "2") (pinfunction "2_2") (pintype "input"))
      (node (ref "R6") (pin "1") (pinfunction "1_1") (pintype "input"))
      (node (ref "U4") (pin "3") (pinfunction "IN_A+_3") (pintype "unspecified"))
    )
    (net (code "33") (name "Net-(U4B-IN_B+)") (class "Default")
      (node (ref "C20") (pin "1") (pinfunction "1_1") (pintype "input"))
      (node (ref "R3") (pin "2") (pinfunction "2_2") (pintype "input"))
      (node (ref "U4") (pin "5") (pinfunction "IN_B+_5") (pintype "unspecified"))
    )
    (net (code "34") (name "Net-(USB1-CC1)") (class "Default")
      (node (ref "R17") (pin "1") (pinfunction "1_1") (pintype "input"))
      (node (ref "USB1") (pin "A5") (pinfunction "CC1_A5") (pintype "unspecified"))
    )
    (net (code "35") (name "Net-(USB1-CC2)") (class "Default")
      (node (ref "R18") (pin "1") (pinfunction "1_1") (pintype "input"))
      (node (ref "USB1") (pin "B5") (pinfunction "CC2_B5") (pintype "unspecified"))
    )
    (net (code "36") (name "PA0") (class "Default")
      (node (ref "H2") (pin "5") (pinfunction "5_5") (pintype "unspecified"))
      (node (ref "U0") (pin "20") (pinfunction "PA0_20") (pintype "unspecified"))
    )
    (net (code "37") (name "PA1") (class "Default")
      (node (ref "H2") (pin "8") (pinfunction "8_8") (pintype "unspecified"))
      (node (ref "U0") (pin "21") (pinfunction "PA1_21") (pintype "unspecified"))
    )
    (net (code "38") (name "PA2") (class "Default")
      (node (ref "H2") (pin "7") (pinfunction "7_7") (pintype "unspecified"))
      (node (ref "U0") (pin "22") (pinfunction "PA2_22") (pintype "unspecified"))
    )
    (net (code "39") (name "PA3") (class "Default")
      (node (ref "H2") (pin "10") (pinfunction "10_10") (pintype "unspecified"))
      (node (ref "U0") (pin "25") (pinfunction "PA3_25") (pintype "unspecified"))
    )
    (net (code "40") (name "PA4") (class "Default")
      (node (ref "H2") (pin "9") (pinfunction "9_9") (pintype "unspecified"))
      (node (ref "U0") (pin "26") (pinfunction "PA4_26") (pintype "unspecified"))
    )
    (net (code "41") (name "PA5") (class "Default")
      (node (ref "H2") (pin "12") (pinfunction "12_12") (pintype "unspecified"))
      (node (ref "U0") (pin "27") (pinfunction "PA5_27") (pintype "unspecified"))
    )
    (net (code "42") (name "PA6") (class "Default")
      (node (ref "H2") (pin "11") (pinfunction "11_11") (pintype "unspecified"))
      (node (ref "U0") (pin "28") (pinfunction "PA6_28") (pintype "unspecified"))
    )
    (net (code "43") (name "PA7") (class "Default")
      (node (ref "H2") (pin "14") (pinfunction "14_14") (pintype "unspecified"))
      (node (ref "U0") (pin "29") (pinfunction "PA7_29") (pintype "unspecified"))
    )
    (net (code "44") (name "PA8") (class "Default")
      (node (ref "H1") (pin "25") (pinfunction "25_25") (pintype "unspecified"))
      (node (ref "U0") (pin "69") (pinfunction "PA8_69") (pintype "unspecified"))
    )
    (net (code "45") (name "PA11") (class "Default")
      (node (ref "H1") (pin "24") (pinfunction "24_24") (pintype "unspecified"))
      (node (ref "U0") (pin "72") (pinfunction "PA11_72") (pintype "unspecified"))
    )
    (net (code "46") (name "PA12") (class "Default")
      (node (ref "H1") (pin "23") (pinfunction "23_23") (pintype "unspecified"))
      (node (ref "U0") (pin "73") (pinfunction "PA12_73") (pintype "unspecified"))
    )
    (net (code "47") (name "PA15") (class "Default")
      (node (ref "H1") (pin "22") (pinfunction "22_22") (pintype "unspecified"))
      (node (ref "U0") (pin "78") (pinfunction "PA15_78") (pintype "unspecified"))
    )
    (net (code "48") (name "PB0") (class "Default")
      (node (ref "H2") (pin "15") (pinfunction "15_15") (pintype "unspecified"))
      (node (ref "U0") (pin "32") (pinfunction "PB0_32") (pintype "unspecified"))
    )
    (net (code "49") (name "PB1") (class "Default")
      (node (ref "H2") (pin "18") (pinfunction "18_18") (pintype "unspecified"))
      (node (ref "U0") (pin "33") (pinfunction "PB1_33") (pintype "unspecified"))
    )
    (net (code "50") (name "PB2") (class "Default")
      (node (ref "H2") (pin "17") (pinfunction "17_17") (pintype "unspecified"))
      (node (ref "U0") (pin "34") (pinfunction "PB2_34") (pintype "unspecified"))
    )
    (net (code "51") (name "PB3") (class "Default")
      (node (ref "H1") (pin "10") (pinfunction "10_10") (pintype "unspecified"))
      (node (ref "U0") (pin "90") (pinfunction "PB3_90") (pintype "unspecified"))
    )
    (net (code "52") (name "PB4") (class "Default")
      (node (ref "H1") (pin "9") (pinfunction "9_9") (pintype "unspecified"))
      (node (ref "U0") (pin "91") (pinfunction "PB4_91") (pintype "unspecified"))
    )
    (net (code "53") (name "PB5") (class "Default")
      (node (ref "H1") (pin "8") (pinfunction "8_8") (pintype "unspecified"))
      (node (ref "U0") (pin "92") (pinfunction "PB5_92") (pintype "unspecified"))
    )
    (net (code "54") (name "PB6") (class "Default")
      (node (ref "H1") (pin "7") (pinfunction "7_7") (pintype "unspecified"))
      (node (ref "U0") (pin "93") (pinfunction "PB6_93") (pintype "unspecified"))
    )
    (net (code "55") (name "PB7") (class "Default")
      (node (ref "H1") (pin "6") (pinfunction "6_6") (pintype "unspecified"))
      (node (ref "U0") (pin "94") (pinfunction "PB7_94") (pintype "unspecified"))
    )
    (net (code "56") (name "PB9") (class "Default")
      (node (ref "H1") (pin "5") (pinfunction "5_5") (pintype "unspecified"))
      (node (ref "U0") (pin "96") (pinfunction "PB9_96") (pintype "unspecified"))
    )
    (net (code "57") (name "PB10") (class "Default")
      (node (ref "H2") (pin "27") (pinfunction "27_27") (pintype "unspecified"))
      (node (ref "U0") (pin "47") (pinfunction "PB10_47") (pintype "unspecified"))
    )
    (net (code "58") (name "PB11") (class "Default")
      (node (ref "H2") (pin "30") (pinfunction "30_30") (pintype "unspecified"))
      (node (ref "U0") (pin "50") (pinfunction "PB11_50") (pintype "unspecified"))
    )
    (net (code "59") (name "PB12") (class "Default")
      (node (ref "H2") (pin "29") (pinfunction "29_29") (pintype "unspecified"))
      (node (ref "U0") (pin "51") (pinfunction "PB12_51") (pintype "unspecified"))
    )
    (net (code "60") (name "PB13") (class "Default")
      (node (ref "H2") (pin "32") (pinfunction "32_32") (pintype "unspecified"))
      (node (ref "U0") (pin "52") (pinfunction "PB13_52") (pintype "unspecified"))
    )
    (net (code "61") (name "PB14") (class "Default")
      (node (ref "H2") (pin "31") (pinfunction "31_31") (pintype "unspecified"))
      (node (ref "U0") (pin "53") (pinfunction "PB14_53") (pintype "unspecified"))
    )
    (net (code "62") (name "PB15") (class "Default")
      (node (ref "H2") (pin "34") (pinfunction "34_34") (pintype "unspecified"))
      (node (ref "U0") (pin "54") (pinfunction "PB15_54") (pintype "unspecified"))
    )
    (net (code "63") (name "PC4") (class "Default")
      (node (ref "H2") (pin "13") (pinfunction "13_13") (pintype "unspecified"))
      (node (ref "U0") (pin "30") (pinfunction "PC4_30") (pintype "unspecified"))
    )
    (net (code "64") (name "PC5") (class "Default")
      (node (ref "H2") (pin "16") (pinfunction "16_16") (pintype "unspecified"))
      (node (ref "U0") (pin "31") (pinfunction "PC5_31") (pintype "unspecified"))
    )
    (net (code "65") (name "PC6") (class "Default")
      (node (ref "H1") (pin "29") (pinfunction "29_29") (pintype "unspecified"))
      (node (ref "U0") (pin "65") (pinfunction "PC6_65") (pintype "unspecified"))
    )
    (net (code "66") (name "PC7") (class "Default")
      (node (ref "H1") (pin "28") (pinfunction "28_28") (pintype "unspecified"))
      (node (ref "U0") (pin "66") (pinfunction "PC7_66") (pintype "unspecified"))
    )
    (net (code "67") (name "PC8") (class "Default")
      (node (ref "H1") (pin "27") (pinfunction "27_27") (pintype "unspecified"))
      (node (ref "U0") (pin "67") (pinfunction "PC8_67") (pintype "unspecified"))
    )
    (net (code "68") (name "PC9") (class "Default")
      (node (ref "H1") (pin "26") (pinfunction "26_26") (pintype "unspecified"))
      (node (ref "U0") (pin "68") (pinfunction "PC9_68") (pintype "unspecified"))
    )
    (net (code "69") (name "PC10") (class "Default")
      (node (ref "H1") (pin "21") (pinfunction "21_21") (pintype "unspecified"))
      (node (ref "U0") (pin "79") (pinfunction "PC10_79") (pintype "unspecified"))
    )
    (net (code "70") (name "PC11") (class "Default")
      (node (ref "H1") (pin "20") (pinfunction "20_20") (pintype "unspecified"))
      (node (ref "U0") (pin "80") (pinfunction "PC11_80") (pintype "unspecified"))
    )
    (net (code "71") (name "PC12") (class "Default")
      (node (ref "H1") (pin "19") (pinfunction "19_19") (pintype "unspecified"))
      (node (ref "U0") (pin "81") (pinfunction "PC12_81") (pintype "unspecified"))
    )
    (net (code "72") (name "PD0") (class "Default")
      (node (ref "H1") (pin "18") (pinfunction "18_18") (pintype "unspecified"))
      (node (ref "U0") (pin "82") (pinfunction "PD0_82") (pintype "unspecified"))
    )
    (net (code "73") (name "PD1") (class "Default")
      (node (ref "H1") (pin "17") (pinfunction "17_17") (pintype "unspecified"))
      (node (ref "U0") (pin "83") (pinfunction "PD1_83") (pintype "unspecified"))
    )
    (net (code "74") (name "PD2") (class "Default")
      (node (ref "H1") (pin "16") (pinfunction "16_16") (pintype "unspecified"))
      (node (ref "U0") (pin "84") (pinfunction "PD2_84") (pintype "unspecified"))
    )
    (net (code "75") (name "PD3") (class "Default")
      (node (ref "H1") (pin "15") (pinfunction "15_15") (pintype "unspecified"))
      (node (ref "U0") (pin "85") (pinfunction "PD3_85") (pintype "unspecified"))
    )
    (net (code "76") (name "PD4") (class "Default")
      (node (ref "H1") (pin "14") (pinfunction "14_14") (pintype "unspecified"))
      (node (ref "U0") (pin "86") (pinfunction "PD4_86") (pintype "unspecified"))
    )
    (net (code "77") (name "PD5") (class "Default")
      (node (ref "H1") (pin "13") (pinfunction "13_13") (pintype "unspecified"))
      (node (ref "U0") (pin "87") (pinfunction "PD5_87") (pintype "unspecified"))
    )
    (net (code "78") (name "PD6") (class "Default")
      (node (ref "H1") (pin "12") (pinfunction "12_12") (pintype "unspecified"))
      (node (ref "U0") (pin "88") (pinfunction "PD6_88") (pintype "unspecified"))
    )
    (net (code "79") (name "PD7") (class "Default")
      (node (ref "H1") (pin "11") (pinfunction "11_11") (pintype "unspecified"))
      (node (ref "U0") (pin "89") (pinfunction "PD7_89") (pintype "unspecified"))
    )
    (net (code "80") (name "PD8") (class "Default")
      (node (ref "H2") (pin "33") (pinfunction "33_33") (pintype "unspecified"))
      (node (ref "U0") (pin "55") (pinfunction "PD8_55") (pintype "unspecified"))
    )
    (net (code "81") (name "PD9") (class "Default")
      (node (ref "H1") (pin "36") (pinfunction "36_36") (pintype "unspecified"))
      (node (ref "U0") (pin "56") (pinfunction "PD9_56") (pintype "unspecified"))
    )
    (net (code "82") (name "PD10") (class "Default")
      (node (ref "H1") (pin "35") (pinfunction "35_35") (pintype "unspecified"))
      (node (ref "U0") (pin "57") (pinfunction "PD10_57") (pintype "unspecified"))
    )
    (net (code "83") (name "PD11") (class "Default")
      (node (ref "H1") (pin "34") (pinfunction "34_34") (pintype "unspecified"))
      (node (ref "U0") (pin "58") (pinfunction "PD11_58") (pintype "unspecified"))
    )
    (net (code "84") (name "PD12") (class "Default")
      (node (ref "H1") (pin "33") (pinfunction "33_33") (pintype "unspecified"))
      (node (ref "U0") (pin "59") (pinfunction "PD12_59") (pintype "unspecified"))
    )
    (net (code "85") (name "PD13") (class "Default")
      (node (ref "H1") (pin "32") (pinfunction "32_32") (pintype "unspecified"))
      (node (ref "U0") (pin "60") (pinfunction "PD13_60") (pintype "unspecified"))
    )
    (net (code "86") (name "PD14") (class "Default")
      (node (ref "H1") (pin "31") (pinfunction "31_31") (pintype "unspecified"))
      (node (ref "U0") (pin "61") (pinfunction "PD14_61") (pintype "unspecified"))
    )
    (net (code "87") (name "PD15") (class "Default")
      (node (ref "H1") (pin "30") (pinfunction "30_30") (pintype "unspecified"))
      (node (ref "U0") (pin "62") (pinfunction "PD15_62") (pintype "unspecified"))
    )
    (net (code "88") (name "PE0") (class "Default")
      (node (ref "H1") (pin "4") (pinfunction "4_4") (pintype "unspecified"))
      (node (ref "U0") (pin "97") (pinfunction "PE0_97") (pintype "unspecified"))
    )
    (net (code "89") (name "PE1") (class "Default")
      (node (ref "H1") (pin "3") (pinfunction "3_3") (pintype "unspecified"))
      (node (ref "U0") (pin "98") (pinfunction "PE1_98") (pintype "unspecified"))
    )
    (net (code "90") (name "PE7") (class "Default")
      (node (ref "H2") (pin "20") (pinfunction "20_20") (pintype "unspecified"))
      (node (ref "U0") (pin "38") (pinfunction "PE7_38") (pintype "unspecified"))
    )
    (net (code "91") (name "PE8") (class "Default")
      (node (ref "H2") (pin "19") (pinfunction "19_19") (pintype "unspecified"))
      (node (ref "U0") (pin "39") (pinfunction "PE8_39") (pintype "unspecified"))
    )
    (net (code "92") (name "PE9") (class "Default")
      (node (ref "H2") (pin "22") (pinfunction "22_22") (pintype "unspecified"))
      (node (ref "U0") (pin "40") (pinfunction "PE9_40") (pintype "unspecified"))
    )
    (net (code "93") (name "PE10") (class "Default")
      (node (ref "H2") (pin "21") (pinfunction "21_21") (pintype "unspecified"))
      (node (ref "U0") (pin "41") (pinfunction "PE10_41") (pintype "unspecified"))
    )
    (net (code "94") (name "PE11") (class "Default")
      (node (ref "H2") (pin "24") (pinfunction "24_24") (pintype "unspecified"))
      (node (ref "U0") (pin "42") (pinfunction "PE11_42") (pintype "unspecified"))
    )
    (net (code "95") (name "PE12") (class "Default")
      (node (ref "H2") (pin "23") (pinfunction "23_23") (pintype "unspecified"))
      (node (ref "U0") (pin "43") (pinfunction "PE12_43") (pintype "unspecified"))
    )
    (net (code "96") (name "PE13") (class "Default")
      (node (ref "H2") (pin "26") (pinfunction "26_26") (pintype "unspecified"))
      (node (ref "U0") (pin "44") (pinfunction "PE13_44") (pintype "unspecified"))
    )
    (net (code "97") (name "PE14") (class "Default")
      (node (ref "H2") (pin "25") (pinfunction "25_25") (pintype "unspecified"))
      (node (ref "U0") (pin "45") (pinfunction "PE14_45") (pintype "unspecified"))
    )
    (net (code "98") (name "PE15") (class "Default")
      (node (ref "H2") (pin "28") (pinfunction "28_28") (pintype "unspecified"))
      (node (ref "U0") (pin "46") (pinfunction "PE15_46") (pintype "unspecified"))
    )
    (net (code "99") (name "PF2") (class "Default")
      (node (ref "H2") (pin "6") (pinfunction "6_6") (pintype "unspecified"))
      (node (ref "U0") (pin "19") (pinfunction "PF2_19") (pintype "unspecified"))
    )
    (net (code "100") (name "PF9") (class "Default")
      (node (ref "H2") (pin "4") (pinfunction "4_4") (pintype "unspecified"))
      (node (ref "U0") (pin "10") (pinfunction "PF9_10") (pintype "unspecified"))
    )
    (net (code "101") (name "PF10") (class "Default")
      (node (ref "H2") (pin "3") (pinfunction "3_3") (pintype "unspecified"))
      (node (ref "U0") (pin "11") (pinfunction "PF10_11") (pintype "unspecified"))
    )
    (net (code "102") (name "SWCLK") (class "Default")
      (node (ref "H0") (pin "1") (pinfunction "1_1") (pintype "unspecified"))
      (node (ref "U0") (pin "77") (pinfunction "PA14_77") (pintype "unspecified"))
    )
    (net (code "103") (name "SWDIO") (class "Default")
      (node (ref "H0") (pin "2") (pinfunction "2_2") (pintype "unspecified"))
      (node (ref "U0") (pin "76") (pinfunction "PA13_76") (pintype "unspecified"))
    )
    (net (code "104") (name "UART_RX") (class "Default")
      (node (ref "U0") (pin "71") (pinfunction "PA10_71") (pintype "unspecified"))
      (node (ref "U5") (pin "8") (pinfunction "TXD_8") (pintype "unspecified"))
    )
    (net (code "105") (name "UART_TX") (class "Default")
      (node (ref "U0") (pin "70") (pinfunction "PA9_70") (pintype "unspecified"))
      (node (ref "U5") (pin "9") (pinfunction "RXD_9") (pintype "unspecified"))
    )
    (net (code "106") (name "USB_DN") (class "Default")
      (node (ref "U5") (pin "2") (pinfunction "UD-_2") (pintype "unspecified"))
      (node (ref "USB1") (pin "A7") (pinfunction "DN1_A7") (pintype "unspecified"))
      (node (ref "USB1") (pin "B7") (pinfunction "DN2_B7") (pintype "unspecified"))
    )
    (net (code "107") (name "USB_DP") (class "Default")
      (node (ref "U5") (pin "1") (pinfunction "UD+_1") (pintype "unspecified"))
      (node (ref "USB1") (pin "A6") (pinfunction "DP1_A6") (pintype "unspecified"))
      (node (ref "USB1") (pin "B6") (pinfunction "DP2_B6") (pintype "unspecified"))
    )
    (net (code "108") (name "VBUS") (class "Default")
      (node (ref "D1") (pin "2") (pinfunction "A_2") (pintype "unspecified"))
      (node (ref "USB1") (pin "A4") (pinfunction "VBUS_A4") (pintype "unspecified"))
      (node (ref "USB1") (pin "A9") (pinfunction "VBUS_A9") (pintype "unspecified"))
      (node (ref "USB1") (pin "B4") (pinfunction "VBUS_B4") (pintype "unspecified"))
      (node (ref "USB1") (pin "B9") (pinfunction "VBUS_B9") (pintype "unspecified"))
    )
    (net (code "109") (name "unconnected-(SW0-Pad1)") (class "Default")
      (node (ref "SW0") (pin "1") (pinfunction "1_1") (pintype "unspecified+no_connect"))
    )
    (net (code "110") (name "unconnected-(SW1-Pad1)") (class "Default")
      (node (ref "SW1") (pin "1") (pinfunction "1_1") (pintype "unspecified+no_connect"))
    )
    (net (code "111") (name "unconnected-(SW2-Pad1)") (class "Default")
      (node (ref "SW2") (pin "1") (pinfunction "1_1") (pintype "unspecified+no_connect"))
    )
    (net (code "112") (name "unconnected-(SW3-Pad1)") (class "Default")
      (node (ref "SW3") (pin "1") (pinfunction "1_1") (pintype "unspecified+no_connect"))
    )
    (net (code "113") (name "unconnected-(SW4-Pad1)") (class "Default")
      (node (ref "SW4") (pin "1") (pinfunction "1_1") (pintype "unspecified+no_connect"))
    )
    (net (code "114") (name "unconnected-(U5-CTS#-Pad5)") (class "Default")
      (node (ref "U5") (pin "5") (pinfunction "CTS#_5") (pintype "unspecified+no_connect"))
    )
    (net (code "115") (name "unconnected-(U5-RTS#-Pad4)") (class "Default")
      (node (ref "U5") (pin "4") (pinfunction "RTS#_4") (pintype "unspecified+no_connect"))
    )
    (net (code "116") (name "unconnected-(U5-TNOW-Pad6)") (class "Default")
      (node (ref "U5") (pin "6") (pinfunction "TNOW_6") (pintype "unspecified+no_connect"))
    )
    (net (code "117") (name "unconnected-(USB1-SUB1-PadA8)") (class "Default")
      (node (ref "USB1") (pin "A8") (pinfunction "SUB1_A8") (pintype "unspecified+no_connect"))
    )
    (net (code "118") (name "unconnected-(USB1-SUB2-PadB8)") (class "Default")
      (node (ref "USB1") (pin "B8") (pinfunction "SUB2_B8") (pintype "unspecified+no_connect"))
    )
  )
)
